# robo2.net
KiCad netlist of a schematic drawn in EAGLE
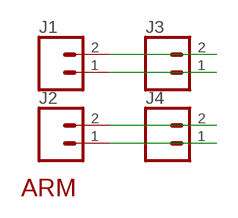
[diagram p0: schematic, sheet 1]

(export (version "E")
  (design (tool "Eeschema 10.0.6"))
  (components
    (comp (ref "J1")
      (value "CONN_02LOCK")
      (footprint "eagle-import:1X02_LOCK")
      (libsource (lib "eagle-import") (part "CONN_02LOCK"))
    )
    (comp (ref "J2")
      (value "CONN_02LOCK")
      (footprint "eagle-import:1X02_LOCK")
      (libsource (lib "eagle-import") (part "CONN_02LOCK"))
    )
    (comp (ref "J3")
      (value "CONN_02LOCK")
      (footprint "eagle-import:1X02_LOCK")
      (libsource (lib "eagle-import") (part "CONN_02LOCK"))
    )
    (comp (ref "J4")
      (value "CONN_02LOCK")
      (footprint "eagle-import:1X02_LOCK")
      (libsource (lib "eagle-import") (part "CONN_02LOCK"))
    )
    (comp (ref "U$1")
      (value "ARMROBO2")
      (footprint "eagle-import:ROBO2")
      (libsource (lib "eagle-import") (part "ARMROBO2"))
    )
  )
  (nets
    (net (code "1") (name "Net-(J1-Pad1)") (class "Default")
      (node (ref "J1") (pin "1") (pinfunction "1_1") (pintype "passive"))
      (node (ref "J3") (pin "1") (pinfunction "1_1") (pintype "passive"))
    )
    (net (code "2") (name "Net-(J1-Pad2)") (class "Default")
      (node (ref "J1") (pin "2") (pinfunction "2_2") (pintype "passive"))
      (node (ref "J3") (pin "2") (pinfunction "2_2") (pintype "passive"))
    )
    (net (code "3") (name "Net-(J2-Pad1)") (class "Default")
      (node (ref "J2") (pin "1") (pinfunction "1_1") (pintype "passive"))
      (node (ref "J4") (pin "1") (pinfunction "1_1") (pintype "passive"))
    )
    (net (code "4") (name "Net-(J2-Pad2)") (class "Default")
      (node (ref "J2") (pin "2") (pinfunction "2_2") (pintype "passive"))
      (node (ref "J4") (pin "2") (pinfunction "2_2") (pintype "passive"))
    )
  )
)
